# MOSFET_and_current_Sense.net
KiCad netlist of a schematic drawn in Altium Designer
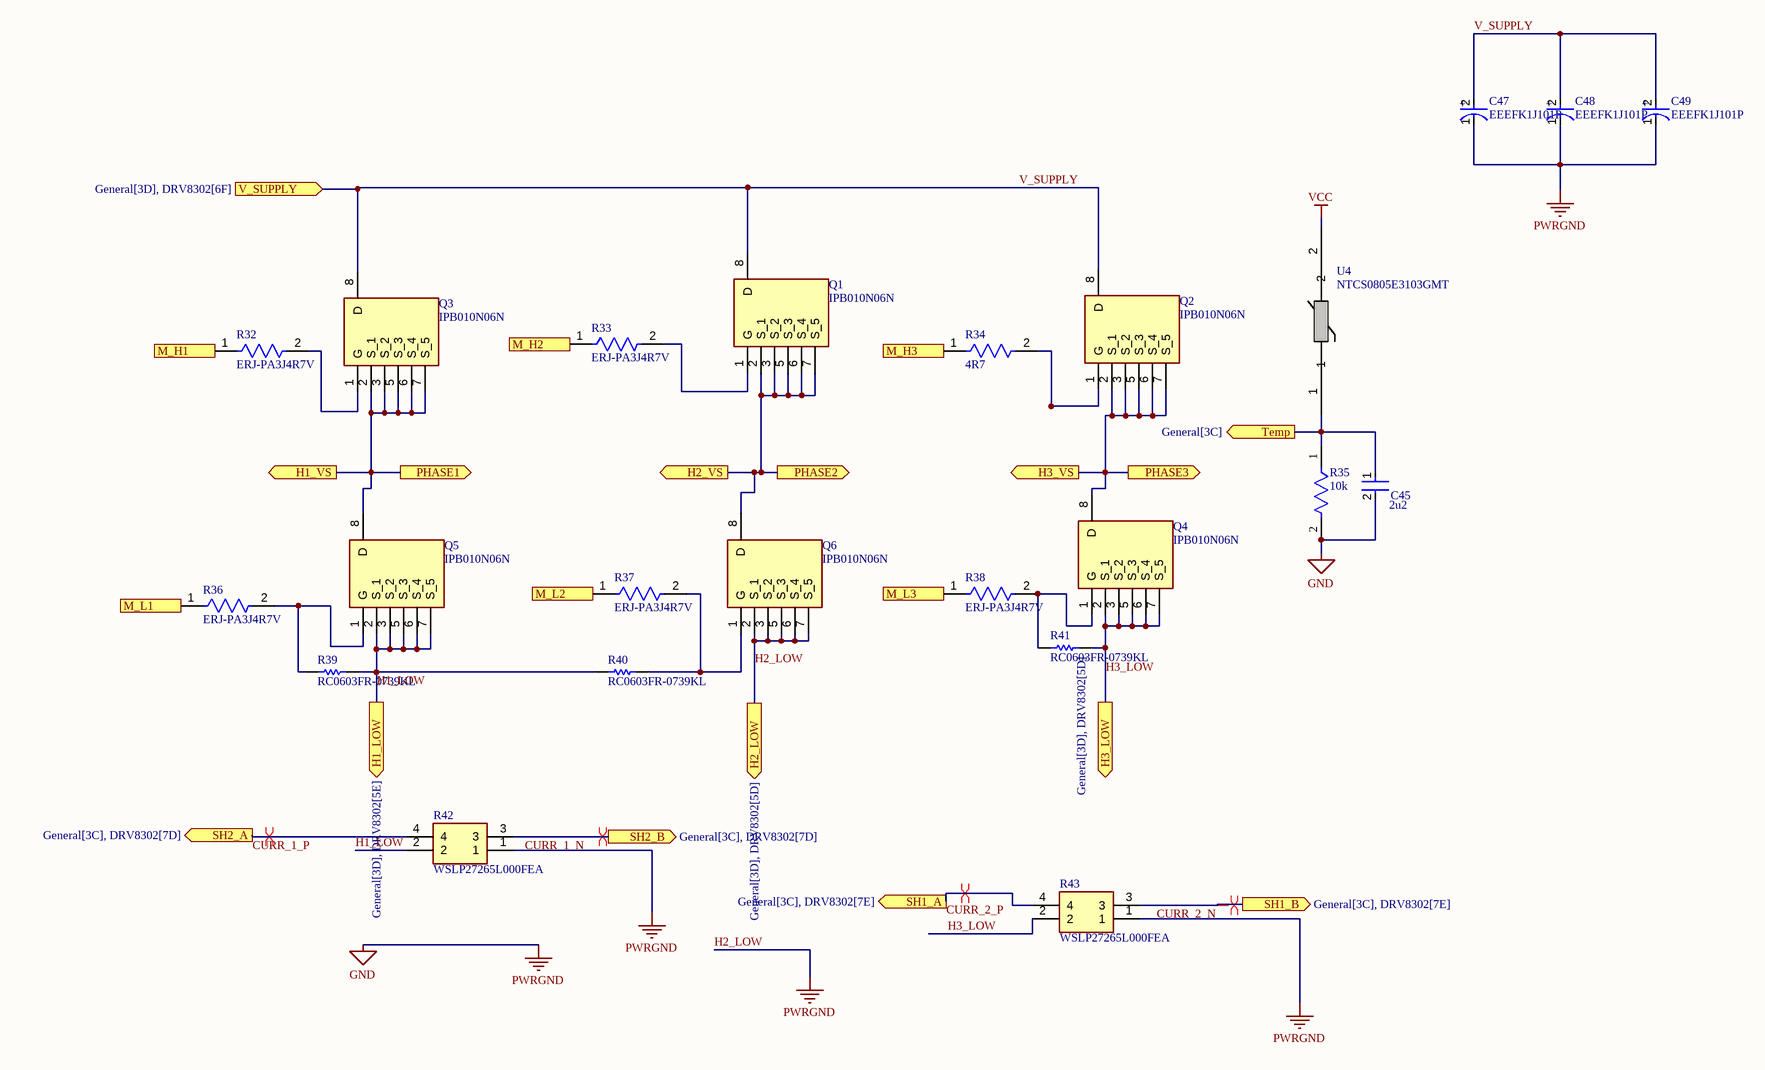
[diagram p0: MOSFET and current Sense.SchDoc]

(export (version "E")
  (design (tool "Eeschema 10.0.6"))
  (components
    (comp (ref "C45")
      (value "2u2")
      (footprint "FP-GRM188-0_1-e0_2_0_5-MFG")
      (description "Chip Multilayer Ceramic Capacitors for General Purpose, 0603, 2.2uF, X7R, 15%, 10%, 10V")
      (fields (field (name "VOLTAGE") "10V") (field (name "TOLERANCE") "10%"))
      (libsource (lib "Altium Content Vault") (part "11868f565c42a9108669ba33697ecf6"))
    )
    (comp (ref "C47")
      (value "EEEFK1J101P")
      (footprint "FP-FKG-MFG")
      (description "CAP ALUM 100UF 20% 63V SMD")
      (fields (field (name "VOLTAGE") "63V") (field (name "TOLERANCE") "20%"))
      (libsource (lib "Altium Content Vault") (part "203bc49f2ac43e59fd269a8c329ed05"))
    )
    (comp (ref "C48")
      (value "EEEFK1J101P")
      (footprint "FP-FKG-MFG")
      (description "CAP ALUM 100UF 20% 63V SMD")
      (fields (field (name "VOLTAGE") "63V") (field (name "TOLERANCE") "20%"))
      (libsource (lib "Altium Content Vault") (part "203bc49f2ac43e59fd269a8c329ed05"))
    )
    (comp (ref "C49")
      (value "EEEFK1J101P")
      (footprint "FP-FKG-MFG")
      (description "CAP ALUM 100UF 20% 63V SMD")
      (fields (field (name "VOLTAGE") "63V") (field (name "TOLERANCE") "20%"))
      (libsource (lib "Altium Content Vault") (part "203bc49f2ac43e59fd269a8c329ed05"))
    )
    (comp (ref "Q1")
      (value "IPB010N06N")
      (footprint "SamacSys:PG-TO263-7-3_3")
      (description "MOSFET (N-Channel)")
      (fields (field (name "MOUSER PART NUMBER") "726-IPB010N06N"))
      (libsource (lib "*") (part "IPB010N06N"))
    )
    (comp (ref "Q2")
      (value "IPB010N06N")
      (footprint "SamacSys:PG-TO263-7-3_3")
      (description "MOSFET (N-Channel)")
      (fields (field (name "MOUSER PART NUMBER") "726-IPB010N06N"))
      (libsource (lib "*") (part "IPB010N06N"))
    )
    (comp (ref "Q3")
      (value "IPB010N06N")
      (footprint "SamacSys:PG-TO263-7-3_3")
      (description "MOSFET (N-Channel)")
      (fields (field (name "MOUSER PART NUMBER") "726-IPB010N06N"))
      (libsource (lib "*") (part "IPB010N06N"))
    )
    (comp (ref "Q4")
      (value "IPB010N06N")
      (footprint "SamacSys:PG-TO263-7-3_3")
      (description "MOSFET (N-Channel)")
      (fields (field (name "MOUSER PART NUMBER") "726-IPB010N06N"))
      (libsource (lib "*") (part "IPB010N06N"))
    )
    (comp (ref "Q5")
      (value "IPB010N06N")
      (footprint "SamacSys:PG-TO263-7-3_3")
      (description "MOSFET (N-Channel)")
      (fields (field (name "MOUSER PART NUMBER") "726-IPB010N06N"))
      (libsource (lib "*") (part "IPB010N06N"))
    )
    (comp (ref "Q6")
      (value "IPB010N06N")
      (footprint "SamacSys:PG-TO263-7-3_3")
      (description "MOSFET (N-Channel)")
      (fields (field (name "MOUSER PART NUMBER") "726-IPB010N06N"))
      (libsource (lib "*") (part "IPB010N06N"))
    )
    (comp (ref "R32")
      (value "ERJ-PA3J4R7V")
      (footprint "FP-ERJPA3-IPC_C")
      (description "RES SMD 4.7 OHM 5% 1/4W 0603")
      (fields (field (name "TOLERANCE") "5%"))
      (libsource (lib "Altium Content Vault") (part "1029c3af85768c4190bb7ad29bc67b5"))
    )
    (comp (ref "R33")
      (value "ERJ-PA3J4R7V")
      (footprint "FP-ERJPA3-IPC_C")
      (description "RES SMD 4.7 OHM 5% 1/4W 0603")
      (fields (field (name "TOLERANCE") "5%"))
      (libsource (lib "Altium Content Vault") (part "1029c3af85768c4190bb7ad29bc67b5"))
    )
    (comp (ref "R34")
      (value "4R7")
      (footprint "FP-ERJPA3-IPC_C")
      (description "RES SMD 4.7 OHM 5% 1/4W 0603")
      (fields (field (name "TOLERANCE") "5%"))
      (libsource (lib "Altium Content Vault") (part "1029c3af85768c4190bb7ad29bc67b5"))
    )
    (comp (ref "R35")
      (value "10k")
      (footprint "FP-ERA3A-IPC_C")
      (description "RES SMD 10K OHM 0.1% 1/10W 0603")
      (fields (field (name "TOLERANCE") "0.1%"))
      (libsource (lib "Altium Content Vault") (part "4e5f8b3dd332802e91518312df5df73"))
    )
    (comp (ref "R36")
      (value "ERJ-PA3J4R7V")
      (footprint "FP-ERJPA3-IPC_C")
      (description "RES SMD 4.7 OHM 5% 1/4W 0603")
      (fields (field (name "TOLERANCE") "5%"))
      (libsource (lib "Altium Content Vault") (part "1029c3af85768c4190bb7ad29bc67b5"))
    )
    (comp (ref "R37")
      (value "ERJ-PA3J4R7V")
      (footprint "FP-ERJPA3-IPC_C")
      (description "RES SMD 4.7 OHM 5% 1/4W 0603")
      (fields (field (name "TOLERANCE") "5%"))
      (libsource (lib "Altium Content Vault") (part "1029c3af85768c4190bb7ad29bc67b5"))
    )
    (comp (ref "R38")
      (value "ERJ-PA3J4R7V")
      (footprint "FP-ERJPA3-IPC_C")
      (description "RES SMD 4.7 OHM 5% 1/4W 0603")
      (fields (field (name "TOLERANCE") "5%"))
      (libsource (lib "Altium Content Vault") (part "1029c3af85768c4190bb7ad29bc67b5"))
    )
    (comp (ref "R39")
      (value "RC0603FR-0739KL")
      (footprint "RESC1608X55X25LL10T15")
      (description "Chip Resistor, 39 KOhm, +/- 1%, 0.1 W, -55 to 155 degC, 0603 (1608 Metric), RoHS, Tape and Reel")
      (fields (field (name "TOLERANCE") "1%") (field (name "MANUFACTURER") "Yageo"))
      (libsource (lib "Altium Content Vault") (part "RES-2"))
    )
    (comp (ref "R40")
      (value "RC0603FR-0739KL")
      (footprint "RESC1608X55X25LL10T15")
      (description "Chip Resistor, 39 KOhm, +/- 1%, 0.1 W, -55 to 155 degC, 0603 (1608 Metric), RoHS, Tape and Reel")
      (fields (field (name "TOLERANCE") "1%") (field (name "MANUFACTURER") "Yageo"))
      (libsource (lib "Altium Content Vault") (part "RES-2"))
    )
    (comp (ref "R41")
      (value "RC0603FR-0739KL")
      (footprint "RESC1608X55X25LL10T15")
      (description "Chip Resistor, 39 KOhm, +/- 1%, 0.1 W, -55 to 155 degC, 0603 (1608 Metric), RoHS, Tape and Reel")
      (fields (field (name "TOLERANCE") "1%") (field (name "MANUFACTURER") "Yageo"))
      (libsource (lib "Altium Content Vault") (part "RES-2"))
    )
    (comp (ref "R42")
      (value "WSLP27265L000FEA")
      (footprint "SamacSys:WSLP27265L000FEA")
      (description "Resistor")
      (fields (field (name "MOUSER PART NUMBER") "71-WSLP27265L000FEA"))
      (libsource (lib "*") (part "WSLP27265L000FEA"))
    )
    (comp (ref "R43")
      (value "WSLP27265L000FEA")
      (footprint "SamacSys:WSLP27265L000FEA")
      (description "Resistor")
      (fields (field (name "MOUSER PART NUMBER") "71-WSLP27265L000FEA"))
      (libsource (lib "*") (part "WSLP27265L000FEA"))
    )
    (comp (ref "U4")
      (value "NTCS0805E3103GMT")
      (footprint "NTCS0805_VIS")
      (fields (field (name "TOLERANCE") "2%"))
      (libsource (lib "Altium Content Vault") (part "NTCS0805E3103GMT"))
    )
  )
  (nets
    (net (code "1") (name "/CURR_1_N") (class "Default")
      (node (ref "R42") (pin "3") (pinfunction "3_3") (pintype "passive"))
    )
    (net (code "2") (name "/CURR_1_P") (class "Default")
      (node (ref "R42") (pin "4") (pinfunction "4_4") (pintype "passive"))
    )
    (net (code "3") (name "/CURR_2_N") (class "Default")
      (node (ref "R43") (pin "3") (pinfunction "3_3") (pintype "passive"))
    )
    (net (code "4") (name "/CURR_2_P") (class "Default")
      (node (ref "R43") (pin "4") (pinfunction "4_4") (pintype "passive"))
    )
    (net (code "5") (name "/H1_LOW") (class "Default")
      (node (ref "Q5") (pin "2") (pinfunction "S_1_2") (pintype "passive"))
      (node (ref "Q5") (pin "3") (pinfunction "S_2_3") (pintype "passive"))
      (node (ref "Q5") (pin "5") (pinfunction "S_3_5") (pintype "passive"))
      (node (ref "Q5") (pin "6") (pinfunction "S_4_6") (pintype "passive"))
      (node (ref "Q5") (pin "7") (pinfunction "S_5_7") (pintype "passive"))
      (node (ref "R39") (pin "2") (pinfunction "2_2") (pintype "passive"))
      (node (ref "R40") (pin "1") (pinfunction "1_1") (pintype "passive"))
      (node (ref "R42") (pin "2") (pinfunction "2_2") (pintype "passive"))
    )
    (net (code "6") (name "/H1_VS") (class "Default")
      (node (ref "Q3") (pin "2") (pinfunction "S_1_2") (pintype "passive"))
      (node (ref "Q3") (pin "3") (pinfunction "S_2_3") (pintype "passive"))
      (node (ref "Q3") (pin "5") (pinfunction "S_3_5") (pintype "passive"))
      (node (ref "Q3") (pin "6") (pinfunction "S_4_6") (pintype "passive"))
      (node (ref "Q3") (pin "7") (pinfunction "S_5_7") (pintype "passive"))
      (node (ref "Q5") (pin "8") (pinfunction "D_8") (pintype "passive"))
    )
    (net (code "7") (name "/H2_VS") (class "Default")
      (node (ref "Q1") (pin "2") (pinfunction "S_1_2") (pintype "passive"))
      (node (ref "Q1") (pin "3") (pinfunction "S_2_3") (pintype "passive"))
      (node (ref "Q1") (pin "5") (pinfunction "S_3_5") (pintype "passive"))
      (node (ref "Q1") (pin "6") (pinfunction "S_4_6") (pintype "passive"))
      (node (ref "Q1") (pin "7") (pinfunction "S_5_7") (pintype "passive"))
      (node (ref "Q6") (pin "8") (pinfunction "D_8") (pintype "passive"))
    )
    (net (code "8") (name "/H3_LOW") (class "Default")
      (node (ref "Q4") (pin "2") (pinfunction "S_1_2") (pintype "passive"))
      (node (ref "Q4") (pin "3") (pinfunction "S_2_3") (pintype "passive"))
      (node (ref "Q4") (pin "5") (pinfunction "S_3_5") (pintype "passive"))
      (node (ref "Q4") (pin "6") (pinfunction "S_4_6") (pintype "passive"))
      (node (ref "Q4") (pin "7") (pinfunction "S_5_7") (pintype "passive"))
      (node (ref "R41") (pin "2") (pinfunction "2_2") (pintype "passive"))
      (node (ref "R43") (pin "2") (pinfunction "2_2") (pintype "passive"))
    )
    (net (code "9") (name "/H3_VS") (class "Default")
      (node (ref "Q2") (pin "2") (pinfunction "S_1_2") (pintype "passive"))
      (node (ref "Q2") (pin "3") (pinfunction "S_2_3") (pintype "passive"))
      (node (ref "Q2") (pin "5") (pinfunction "S_3_5") (pintype "passive"))
      (node (ref "Q2") (pin "6") (pinfunction "S_4_6") (pintype "passive"))
      (node (ref "Q2") (pin "7") (pinfunction "S_5_7") (pintype "passive"))
      (node (ref "Q4") (pin "8") (pinfunction "D_8") (pintype "passive"))
    )
    (net (code "10") (name "/M_H1") (class "Default")
      (node (ref "R32") (pin "1") (pinfunction "1_1") (pintype "passive"))
    )
    (net (code "11") (name "/M_H2") (class "Default")
      (node (ref "R33") (pin "1") (pinfunction "1_1") (pintype "passive"))
    )
    (net (code "12") (name "/M_H3") (class "Default")
      (node (ref "R34") (pin "1") (pinfunction "1_1") (pintype "passive"))
    )
    (net (code "13") (name "/M_L1") (class "Default")
      (node (ref "R36") (pin "1") (pinfunction "1_1") (pintype "passive"))
    )
    (net (code "14") (name "/M_L2") (class "Default")
      (node (ref "R37") (pin "1") (pinfunction "1_1") (pintype "passive"))
    )
    (net (code "15") (name "/M_L3") (class "Default")
      (node (ref "R38") (pin "1") (pinfunction "1_1") (pintype "passive"))
    )
    (net (code "16") (name "/Temp") (class "Default")
      (node (ref "C45") (pin "1") (pinfunction "1_1") (pintype "passive"))
      (node (ref "R35") (pin "1") (pinfunction "1_1") (pintype "passive"))
      (node (ref "U4") (pin "1") (pinfunction "1_1") (pintype "passive"))
    )
    (net (code "17") (name "/V_SUPPLY") (class "Default")
      (node (ref "C47") (pin "2") (pinfunction "A_2") (pintype "passive"))
      (node (ref "C48") (pin "2") (pinfunction "A_2") (pintype "passive"))
      (node (ref "C49") (pin "2") (pinfunction "A_2") (pintype "passive"))
      (node (ref "Q1") (pin "8") (pinfunction "D_8") (pintype "passive"))
      (node (ref "Q2") (pin "8") (pinfunction "D_8") (pintype "passive"))
      (node (ref "Q3") (pin "8") (pinfunction "D_8") (pintype "passive"))
    )
    (net (code "18") (name "GND") (class "Default")
      (node (ref "C45") (pin "2") (pinfunction "2_2") (pintype "passive"))
      (node (ref "C47") (pin "1") (pinfunction "C_1") (pintype "passive"))
      (node (ref "C48") (pin "1") (pinfunction "C_1") (pintype "passive"))
      (node (ref "C49") (pin "1") (pinfunction "C_1") (pintype "passive"))
      (node (ref "Q6") (pin "2") (pinfunction "S_1_2") (pintype "passive"))
      (node (ref "Q6") (pin "3") (pinfunction "S_2_3") (pintype "passive"))
      (node (ref "Q6") (pin "5") (pinfunction "S_3_5") (pintype "passive"))
      (node (ref "Q6") (pin "6") (pinfunction "S_4_6") (pintype "passive"))
      (node (ref "Q6") (pin "7") (pinfunction "S_5_7") (pintype "passive"))
      (node (ref "R35") (pin "2") (pinfunction "2_2") (pintype "passive"))
      (node (ref "R42") (pin "1") (pinfunction "1_1") (pintype "passive"))
      (node (ref "R43") (pin "1") (pinfunction "1_1") (pintype "passive"))
    )
    (net (code "19") (name "Net-(Q1-G)") (class "Default")
      (node (ref "Q1") (pin "1") (pinfunction "G_1") (pintype "passive"))
      (node (ref "R33") (pin "2") (pinfunction "2_2") (pintype "passive"))
    )
    (net (code "20") (name "Net-(Q2-G)") (class "Default")
      (node (ref "Q2") (pin "1") (pinfunction "G_1") (pintype "passive"))
      (node (ref "R34") (pin "2") (pinfunction "2_2") (pintype "passive"))
    )
    (net (code "21") (name "Net-(Q3-G)") (class "Default")
      (node (ref "Q3") (pin "1") (pinfunction "G_1") (pintype "passive"))
      (node (ref "R32") (pin "2") (pinfunction "2_2") (pintype "passive"))
    )
    (net (code "22") (name "Net-(Q4-G)") (class "Default")
      (node (ref "Q4") (pin "1") (pinfunction "G_1") (pintype "passive"))
      (node (ref "R38") (pin "2") (pinfunction "2_2") (pintype "passive"))
      (node (ref "R41") (pin "1") (pinfunction "1_1") (pintype "passive"))
    )
    (net (code "23") (name "Net-(Q5-G)") (class "Default")
      (node (ref "Q5") (pin "1") (pinfunction "G_1") (pintype "passive"))
      (node (ref "R36") (pin "2") (pinfunction "2_2") (pintype "passive"))
      (node (ref "R39") (pin "1") (pinfunction "1_1") (pintype "passive"))
    )
    (net (code "24") (name "Net-(Q6-G)") (class "Default")
      (node (ref "Q6") (pin "1") (pinfunction "G_1") (pintype "passive"))
      (node (ref "R37") (pin "2") (pinfunction "2_2") (pintype "passive"))
      (node (ref "R40") (pin "2") (pinfunction "2_2") (pintype "passive"))
    )
    (net (code "25") (name "VCC") (class "Default")
      (node (ref "U4") (pin "2") (pinfunction "2_2") (pintype "passive"))
    )
  )
)
